# EBH-10.net
KiCad netlist of a schematic drawn in EAGLE
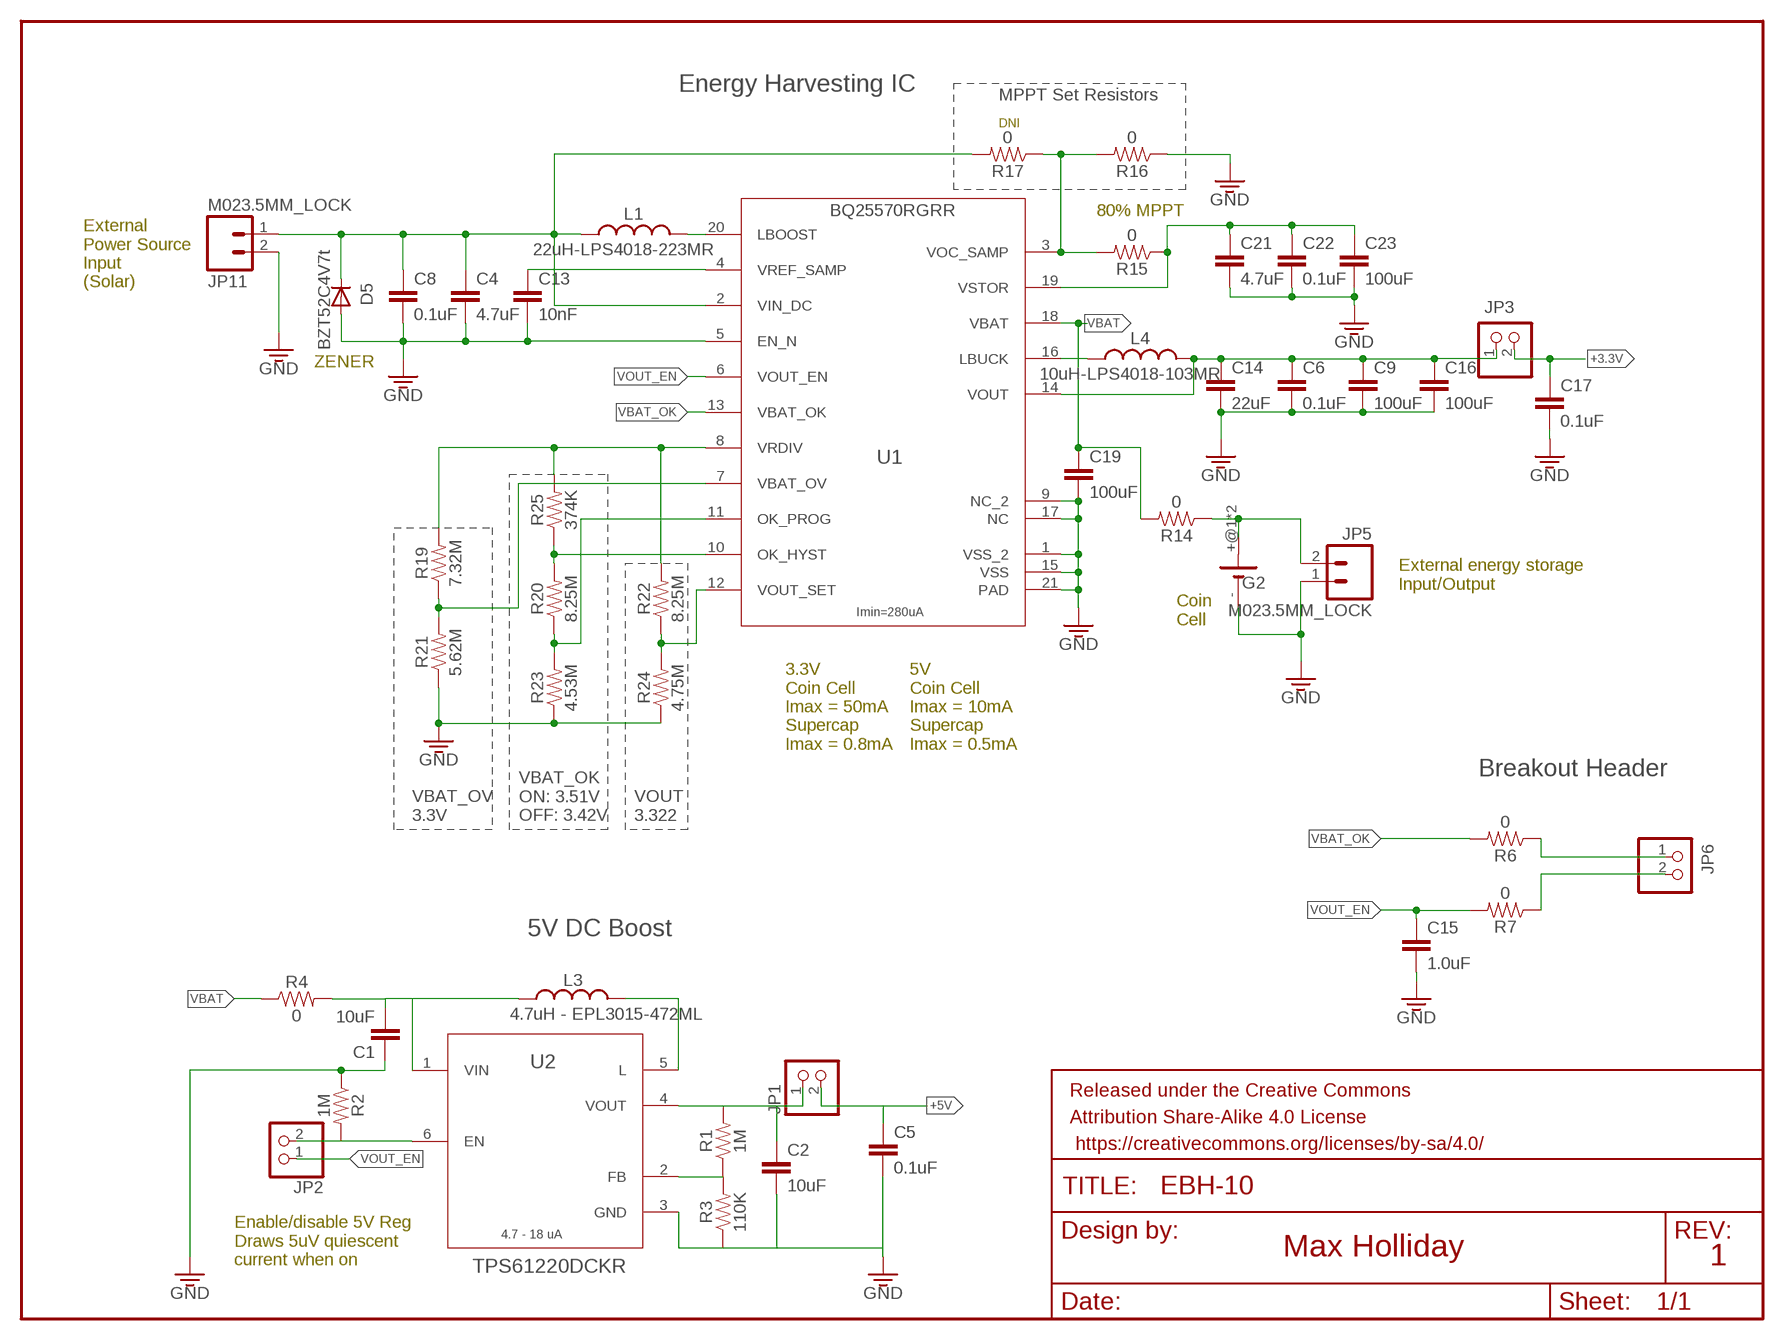
[diagram p0: schematic, sheet 1]

(export (version "E")
  (design (tool "Eeschema 10.0.6"))
  (components
    (comp (ref "C1")
      (value "10uF")
      (footprint "eagle-import:0603")
      (libsource (lib "eagle-import") (part "10UF-0603-6.3V-20%"))
    )
    (comp (ref "C2")
      (value "10uF")
      (footprint "eagle-import:0603")
      (libsource (lib "eagle-import") (part "10UF-0603-6.3V-20%"))
    )
    (comp (ref "C4")
      (value "4.7uF")
      (footprint "eagle-import:0603")
      (libsource (lib "eagle-import") (part "4.7UF0603"))
    )
    (comp (ref "C5")
      (value "0.1uF")
      (footprint "eagle-import:0603")
      (libsource (lib "eagle-import") (part "0.1UF-0603-25V-(+80/-20%)"))
    )
    (comp (ref "C6")
      (value "0.1uF")
      (footprint "eagle-import:0603")
      (libsource (lib "eagle-import") (part "0.1UF-0603-25V-(+80/-20%)"))
    )
    (comp (ref "C8")
      (value "0.1uF")
      (footprint "eagle-import:0603")
      (libsource (lib "eagle-import") (part "0.1UF-0603-25V-(+80/-20%)"))
    )
    (comp (ref "C9")
      (value "100uF")
      (footprint "eagle-import:0603")
      (libsource (lib "eagle-import") (part "0.1UF-0603-25V-(+80/-20%)"))
    )
    (comp (ref "C13")
      (value "10nF")
      (footprint "eagle-import:0603")
      (libsource (lib "eagle-import") (part "10NF-0603-50V-10%"))
    )
    (comp (ref "C14")
      (value "22uF")
      (footprint "eagle-import:0805")
      (libsource (lib "eagle-import") (part "22UF-0805-6.3V-20%"))
    )
    (comp (ref "C15")
      (value "1.0uF")
      (footprint "eagle-import:0603")
      (libsource (lib "eagle-import") (part "1.0UF-0603-16V-10%"))
    )
    (comp (ref "C16")
      (value "100uF")
      (footprint "eagle-import:0603")
      (libsource (lib "eagle-import") (part "0.1UF-0603-25V-(+80/-20%)"))
    )
    (comp (ref "C17")
      (value "0.1uF")
      (footprint "eagle-import:0603")
      (libsource (lib "eagle-import") (part "0.1UF-0603-25V-(+80/-20%)"))
    )
    (comp (ref "C19")
      (value "100uF")
      (footprint "eagle-import:0603")
      (libsource (lib "eagle-import") (part "0.1UF-0603-25V-(+80/-20%)"))
    )
    (comp (ref "C21")
      (value "4.7uF")
      (footprint "eagle-import:0603")
      (libsource (lib "eagle-import") (part "4.7UF0603"))
    )
    (comp (ref "C22")
      (value "0.1uF")
      (footprint "eagle-import:0603")
      (libsource (lib "eagle-import") (part "0.1UF-0603-25V-(+80/-20%)"))
    )
    (comp (ref "C23")
      (value "100uF")
      (footprint "eagle-import:0603")
      (libsource (lib "eagle-import") (part "0.1UF-0603-25V-(+80/-20%)"))
    )
    (comp (ref "D5")
      (value "BZT52C4V7t")
      (footprint "eagle-import:SOD523")
      (libsource (lib "eagle-import") (part "DIODE-SOD523"))
    )
    (comp (ref "FRAME1")
      (value "FRAME-LETTERNO_PACKAGE")
      (footprint "eagle-import:DUMMY")
      (fields (field (name "DESIGNER") "Nobody"))
      (libsource (lib "eagle-import") (part "FRAME-LETTERNO_PACKAGE"))
    )
    (comp (ref "G2")
      (value "10MM_SM_COIN_CELL_CLIP")
      (footprint "eagle-import:10MM_SM_COIN_CELL_CLIP")
      (libsource (lib "eagle-import") (part "10MM_SM_COIN_CELL_CLIP"))
    )
    (comp (ref "JP1")
      (value "PINHD-1X2")
      (footprint "eagle-import:1X02")
      (libsource (lib "eagle-import") (part "PINHD-1X2"))
    )
    (comp (ref "JP2")
      (value "PINHD-1X2")
      (footprint "eagle-import:1X02")
      (libsource (lib "eagle-import") (part "PINHD-1X2"))
    )
    (comp (ref "JP3")
      (value "PINHD-1X2")
      (footprint "eagle-import:1X02")
      (libsource (lib "eagle-import") (part "PINHD-1X2"))
    )
    (comp (ref "JP5")
      (value "M023.5MM_LOCK")
      (footprint "eagle-import:SCREWTERMINAL-3.5MM-2_LOCK")
      (libsource (lib "eagle-import") (part "M023.5MM_LOCK"))
    )
    (comp (ref "JP6")
      (value "PINHD-1X2")
      (footprint "eagle-import:1X02")
      (libsource (lib "eagle-import") (part "PINHD-1X2"))
    )
    (comp (ref "JP11")
      (value "M023.5MM_LOCK")
      (footprint "eagle-import:SCREWTERMINAL-3.5MM-2_LOCK")
      (libsource (lib "eagle-import") (part "M023.5MM_LOCK"))
    )
    (comp (ref "L1")
      (value "22uH-LPS4018-223MR")
      (footprint "eagle-import:LPS4018")
      (libsource (lib "eagle-import") (part "COILCRAFT-LPS4018"))
    )
    (comp (ref "L3")
      (value "4.7uH - EPL3015-472ML")
      (footprint "eagle-import:DFE322512C")
      (libsource (lib "eagle-import") (part "INDUCTORDFE322512C"))
    )
    (comp (ref "L4")
      (value "10uH-LPS4018-103MR")
      (footprint "eagle-import:LPS4018")
      (libsource (lib "eagle-import") (part "COILCRAFT-LPS4018"))
    )
    (comp (ref "R1")
      (value "1M")
      (footprint "eagle-import:0603")
      (libsource (lib "eagle-import") (part "1MOHM-0603-1/4W-5%"))
    )
    (comp (ref "R2")
      (value "1M")
      (footprint "eagle-import:0603")
      (libsource (lib "eagle-import") (part "1MOHM-0603-1/4W-5%"))
    )
    (comp (ref "R3")
      (value "110K")
      (footprint "eagle-import:0603")
      (libsource (lib "eagle-import") (part "100KOHM-0603-1/10W-1%"))
    )
    (comp (ref "R4")
      (value "0")
      (footprint "eagle-import:0603")
      (libsource (lib "eagle-import") (part "0OHM-0603-1/10W-5%"))
    )
    (comp (ref "R6")
      (value "0")
      (footprint "eagle-import:0603")
      (libsource (lib "eagle-import") (part "0OHM-0603-1/10W-5%"))
    )
    (comp (ref "R7")
      (value "0")
      (footprint "eagle-import:0603")
      (libsource (lib "eagle-import") (part "0OHM-0603-1/10W-5%"))
    )
    (comp (ref "R14")
      (value "0")
      (footprint "eagle-import:0603")
      (libsource (lib "eagle-import") (part "0OHM-0603-1/10W-5%"))
    )
    (comp (ref "R15")
      (value "0")
      (footprint "eagle-import:0603")
      (libsource (lib "eagle-import") (part "0OHM-0603-1/10W-5%"))
    )
    (comp (ref "R16")
      (value "0")
      (footprint "eagle-import:0603")
      (libsource (lib "eagle-import") (part "0OHM-0603-1/10W-5%"))
    )
    (comp (ref "R17")
      (value "0")
      (footprint "eagle-import:0603")
      (libsource (lib "eagle-import") (part "0OHM-0603-1/10W-5%"))
    )
    (comp (ref "R19")
      (value "7.32M")
      (footprint "eagle-import:0603")
      (libsource (lib "eagle-import") (part "1MOHM-0603-1/4W-5%"))
    )
    (comp (ref "R20")
      (value "8.25M")
      (footprint "eagle-import:0603")
      (libsource (lib "eagle-import") (part "1MOHM-0603-1/4W-5%"))
    )
    (comp (ref "R21")
      (value "5.62M")
      (footprint "eagle-import:0603")
      (libsource (lib "eagle-import") (part "1MOHM-0603-1/4W-5%"))
    )
    (comp (ref "R22")
      (value "8.25M")
      (footprint "eagle-import:0603")
      (libsource (lib "eagle-import") (part "1MOHM-0603-1/4W-5%"))
    )
    (comp (ref "R23")
      (value "4.53M")
      (footprint "eagle-import:0603")
      (libsource (lib "eagle-import") (part "1MOHM-0603-1/4W-5%"))
    )
    (comp (ref "R24")
      (value "4.75M")
      (footprint "eagle-import:0603")
      (libsource (lib "eagle-import") (part "1MOHM-0603-1/4W-5%"))
    )
    (comp (ref "R25")
      (value "374K")
      (footprint "eagle-import:0603")
      (libsource (lib "eagle-import") (part "1MOHM-0603-1/4W-5%"))
    )
    (comp (ref "U1")
      (value "Value")
      (footprint "eagle-import:RGR0020A")
      (fields
        (field (name "ALTERNATEPARTNUMBER") "BQ25570RGRT")
        (field (name "MANUFACTURER") "Texas Instruments")
        (field (name "PARTNUMBER") "BQ25570RGRR")
      )
      (libsource (lib "eagle-import") (part "BQ25570RGRR"))
    )
    (comp (ref "U2")
      (value "TPS61220DCKR")
      (footprint "eagle-import:DCK0006A")
      (fields (field (name "MANUFACTURER") "Texas Instruments") (field (name "PARTNUMBER") "TPS61220DCK"))
      (libsource (lib "eagle-import") (part "TPS61220DCKR"))
    )
  )
  (nets
    (net (code "1") (name "+3.3V") (class "Default")
      (node (ref "C17") (pin "1") (pinfunction "1_1") (pintype "passive"))
      (node (ref "JP3") (pin "2") (pinfunction "2_2") (pintype "passive"))
    )
    (net (code "2") (name "+5V") (class "Default")
      (node (ref "C5") (pin "1") (pinfunction "1_1") (pintype "passive"))
      (node (ref "JP1") (pin "2") (pinfunction "2_2") (pintype "passive"))
    )
    (net (code "3") (name "GND") (class "Default")
      (node (ref "C1") (pin "1") (pinfunction "1_1") (pintype "passive"))
      (node (ref "C13") (pin "2") (pinfunction "2_2") (pintype "passive"))
      (node (ref "C14") (pin "2") (pinfunction "2_2") (pintype "passive"))
      (node (ref "C15") (pin "2") (pinfunction "2_2") (pintype "passive"))
      (node (ref "C16") (pin "2") (pinfunction "2_2") (pintype "passive"))
      (node (ref "C17") (pin "2") (pinfunction "2_2") (pintype "passive"))
      (node (ref "C19") (pin "2") (pinfunction "2_2") (pintype "passive"))
      (node (ref "C2") (pin "2") (pinfunction "2_2") (pintype "passive"))
      (node (ref "C21") (pin "2") (pinfunction "2_2") (pintype "passive"))
      (node (ref "C22") (pin "2") (pinfunction "2_2") (pintype "passive"))
      (node (ref "C23") (pin "2") (pinfunction "2_2") (pintype "passive"))
      (node (ref "C4") (pin "2") (pinfunction "2_2") (pintype "passive"))
      (node (ref "C5") (pin "2") (pinfunction "2_2") (pintype "passive"))
      (node (ref "C6") (pin "2") (pinfunction "2_2") (pintype "passive"))
      (node (ref "C8") (pin "2") (pinfunction "2_2") (pintype "passive"))
      (node (ref "C9") (pin "2") (pinfunction "2_2") (pintype "passive"))
      (node (ref "D5") (pin "A") (pinfunction "A_A") (pintype "passive"))
      (node (ref "G2") (pin "-") (pinfunction "-_-") (pintype "passive"))
      (node (ref "JP11") (pin "2") (pinfunction "2_2") (pintype "passive"))
      (node (ref "JP5") (pin "1") (pinfunction "1_1") (pintype "passive"))
      (node (ref "R16") (pin "1") (pinfunction "1_1") (pintype "passive"))
      (node (ref "R2") (pin "1") (pinfunction "1_1") (pintype "passive"))
      (node (ref "R21") (pin "1") (pinfunction "1_1") (pintype "passive"))
      (node (ref "R23") (pin "1") (pinfunction "1_1") (pintype "passive"))
      (node (ref "R24") (pin "1") (pinfunction "1_1") (pintype "passive"))
      (node (ref "R3") (pin "1") (pinfunction "1_1") (pintype "passive"))
      (node (ref "U1") (pin "1") (pinfunction "VSS_2_1") (pintype "power_in"))
      (node (ref "U1") (pin "15") (pinfunction "VSS_15") (pintype "power_in"))
      (node (ref "U1") (pin "17") (pinfunction "NC_17") (pintype "passive"))
      (node (ref "U1") (pin "21") (pinfunction "PAD_21") (pintype "power_in"))
      (node (ref "U1") (pin "5") (pinfunction "EN_N_5") (pintype "input"))
      (node (ref "U1") (pin "9") (pinfunction "NC_2_9") (pintype "power_in"))
      (node (ref "U2") (pin "3") (pinfunction "GND_3") (pintype "power_in"))
    )
    (net (code "4") (name "Net-(G2-+-Pad+@1)") (class "Default")
      (node (ref "G2") (pin "+@1") (pinfunction "+_+@1") (pintype "passive"))
      (node (ref "G2") (pin "+@2") (pinfunction "+_+@2") (pintype "passive"))
      (node (ref "JP5") (pin "2") (pinfunction "2_2") (pintype "passive"))
      (node (ref "R14") (pin "1") (pinfunction "1_1") (pintype "passive"))
    )
    (net (code "5") (name "Net-(JP6-Pad1)") (class "Default")
      (node (ref "JP6") (pin "1") (pinfunction "1_1") (pintype "passive"))
      (node (ref "R6") (pin "1") (pinfunction "1_1") (pintype "passive"))
    )
    (net (code "6") (name "Net-(JP6-Pad2)") (class "Default")
      (node (ref "JP6") (pin "2") (pinfunction "2_2") (pintype "passive"))
      (node (ref "R7") (pin "1") (pinfunction "1_1") (pintype "passive"))
    )
    (net (code "7") (name "Net-(L3-1)") (class "Default")
      (node (ref "C1") (pin "2") (pinfunction "2_2") (pintype "passive"))
      (node (ref "L3") (pin "P$1") (pinfunction "1_P$1") (pintype "bidirectional"))
      (node (ref "R4") (pin "2") (pinfunction "2_2") (pintype "passive"))
      (node (ref "U2") (pin "1") (pinfunction "VIN_1") (pintype "power_in"))
    )
    (net (code "8") (name "Net-(L3-2)") (class "Default")
      (node (ref "L3") (pin "P$2") (pinfunction "2_P$2") (pintype "bidirectional"))
      (node (ref "U2") (pin "5") (pinfunction "L_5") (pintype "passive"))
    )
    (net (code "9") (name "Net-(U1-LBOOST)") (class "Default")
      (node (ref "L1") (pin "2") (pinfunction "2_2") (pintype "passive"))
      (node (ref "U1") (pin "20") (pinfunction "LBOOST_20") (pintype "input"))
    )
    (net (code "10") (name "Net-(U1-LBUCK)") (class "Default")
      (node (ref "L4") (pin "1") (pinfunction "1_1") (pintype "passive"))
      (node (ref "U1") (pin "16") (pinfunction "LBUCK_16") (pintype "passive"))
    )
    (net (code "11") (name "Net-(U1-OK_HYST)") (class "Default")
      (node (ref "R20") (pin "2") (pinfunction "2_2") (pintype "passive"))
      (node (ref "R25") (pin "1") (pinfunction "1_1") (pintype "passive"))
      (node (ref "U1") (pin "10") (pinfunction "OK_HYST_10") (pintype "input"))
    )
    (net (code "12") (name "Net-(U1-OK_PROG)") (class "Default")
      (node (ref "R20") (pin "1") (pinfunction "1_1") (pintype "passive"))
      (node (ref "R23") (pin "2") (pinfunction "2_2") (pintype "passive"))
      (node (ref "U1") (pin "11") (pinfunction "OK_PROG_11") (pintype "input"))
    )
    (net (code "13") (name "Net-(U1-VBAT_OV)") (class "Default")
      (node (ref "R19") (pin "1") (pinfunction "1_1") (pintype "passive"))
      (node (ref "R21") (pin "2") (pinfunction "2_2") (pintype "passive"))
      (node (ref "U1") (pin "7") (pinfunction "VBAT_OV_7") (pintype "input"))
    )
    (net (code "14") (name "Net-(U1-VIN_DC)") (class "Default")
      (node (ref "C4") (pin "1") (pinfunction "1_1") (pintype "passive"))
      (node (ref "C8") (pin "1") (pinfunction "1_1") (pintype "passive"))
      (node (ref "D5") (pin "C") (pinfunction "C_C") (pintype "passive"))
      (node (ref "JP11") (pin "1") (pinfunction "1_1") (pintype "passive"))
      (node (ref "L1") (pin "1") (pinfunction "1_1") (pintype "passive"))
      (node (ref "R17") (pin "2") (pinfunction "2_2") (pintype "passive"))
      (node (ref "U1") (pin "2") (pinfunction "VIN_DC_2") (pintype "power_in"))
    )
    (net (code "15") (name "Net-(U1-VOC_SAMP)") (class "Default")
      (node (ref "R15") (pin "2") (pinfunction "2_2") (pintype "passive"))
      (node (ref "R16") (pin "2") (pinfunction "2_2") (pintype "passive"))
      (node (ref "R17") (pin "1") (pinfunction "1_1") (pintype "passive"))
      (node (ref "U1") (pin "3") (pinfunction "VOC_SAMP_3") (pintype "input"))
    )
    (net (code "16") (name "Net-(U1-VOUT)") (class "Default")
      (node (ref "C14") (pin "1") (pinfunction "1_1") (pintype "passive"))
      (node (ref "C16") (pin "1") (pinfunction "1_1") (pintype "passive"))
      (node (ref "C6") (pin "1") (pinfunction "1_1") (pintype "passive"))
      (node (ref "C9") (pin "1") (pinfunction "1_1") (pintype "passive"))
      (node (ref "JP3") (pin "1") (pinfunction "1_1") (pintype "passive"))
      (node (ref "L4") (pin "2") (pinfunction "2_2") (pintype "passive"))
      (node (ref "U1") (pin "14") (pinfunction "VOUT_14") (pintype "power_in"))
    )
    (net (code "17") (name "Net-(U1-VOUT_SET)") (class "Default")
      (node (ref "R22") (pin "1") (pinfunction "1_1") (pintype "passive"))
      (node (ref "R24") (pin "2") (pinfunction "2_2") (pintype "passive"))
      (node (ref "U1") (pin "12") (pinfunction "VOUT_SET_12") (pintype "input"))
    )
    (net (code "18") (name "Net-(U1-VRDIV)") (class "Default")
      (node (ref "R19") (pin "2") (pinfunction "2_2") (pintype "passive"))
      (node (ref "R22") (pin "2") (pinfunction "2_2") (pintype "passive"))
      (node (ref "R25") (pin "2") (pinfunction "2_2") (pintype "passive"))
      (node (ref "U1") (pin "8") (pinfunction "VRDIV_8") (pintype "output"))
    )
    (net (code "19") (name "Net-(U1-VREF_SAMP)") (class "Default")
      (node (ref "C13") (pin "1") (pinfunction "1_1") (pintype "passive"))
      (node (ref "U1") (pin "4") (pinfunction "VREF_SAMP_4") (pintype "input"))
    )
    (net (code "20") (name "Net-(U1-VSTOR)") (class "Default")
      (node (ref "C21") (pin "1") (pinfunction "1_1") (pintype "passive"))
      (node (ref "C22") (pin "1") (pinfunction "1_1") (pintype "passive"))
      (node (ref "C23") (pin "1") (pinfunction "1_1") (pintype "passive"))
      (node (ref "R15") (pin "1") (pinfunction "1_1") (pintype "passive"))
      (node (ref "U1") (pin "19") (pinfunction "VSTOR_19") (pintype "power_in"))
    )
    (net (code "21") (name "Net-(U2-EN)") (class "Default")
      (node (ref "JP2") (pin "2") (pinfunction "2_2") (pintype "passive"))
      (node (ref "R2") (pin "2") (pinfunction "2_2") (pintype "passive"))
      (node (ref "U2") (pin "6") (pinfunction "EN_6") (pintype "input"))
    )
    (net (code "22") (name "Net-(U2-FB)") (class "Default")
      (node (ref "R1") (pin "1") (pinfunction "1_1") (pintype "passive"))
      (node (ref "R3") (pin "2") (pinfunction "2_2") (pintype "passive"))
      (node (ref "U2") (pin "2") (pinfunction "FB_2") (pintype "input"))
    )
    (net (code "23") (name "Net-(U2-VOUT)") (class "Default")
      (node (ref "C2") (pin "1") (pinfunction "1_1") (pintype "passive"))
      (node (ref "JP1") (pin "1") (pinfunction "1_1") (pintype "passive"))
      (node (ref "R1") (pin "2") (pinfunction "2_2") (pintype "passive"))
      (node (ref "U2") (pin "4") (pinfunction "VOUT_4") (pintype "power_in"))
    )
    (net (code "24") (name "VBAT") (class "Default")
      (node (ref "C19") (pin "1") (pinfunction "1_1") (pintype "passive"))
      (node (ref "R14") (pin "2") (pinfunction "2_2") (pintype "passive"))
      (node (ref "R4") (pin "1") (pinfunction "1_1") (pintype "passive"))
      (node (ref "U1") (pin "18") (pinfunction "VBAT_18") (pintype "bidirectional"))
    )
    (net (code "25") (name "VBAT_OK") (class "Default")
      (node (ref "R6") (pin "2") (pinfunction "2_2") (pintype "passive"))
      (node (ref "U1") (pin "13") (pinfunction "VBAT_OK_13") (pintype "output"))
    )
    (net (code "26") (name "VOUT_EN") (class "Default")
      (node (ref "C15") (pin "1") (pinfunction "1_1") (pintype "passive"))
      (node (ref "JP2") (pin "1") (pinfunction "1_1") (pintype "passive"))
      (node (ref "R7") (pin "2") (pinfunction "2_2") (pintype "passive"))
      (node (ref "U1") (pin "6") (pinfunction "VOUT_EN_6") (pintype "input"))
    )
  )
)
